# 2_RK3399_SDRAM.net
KiCad netlist of a schematic drawn in Altium Designer
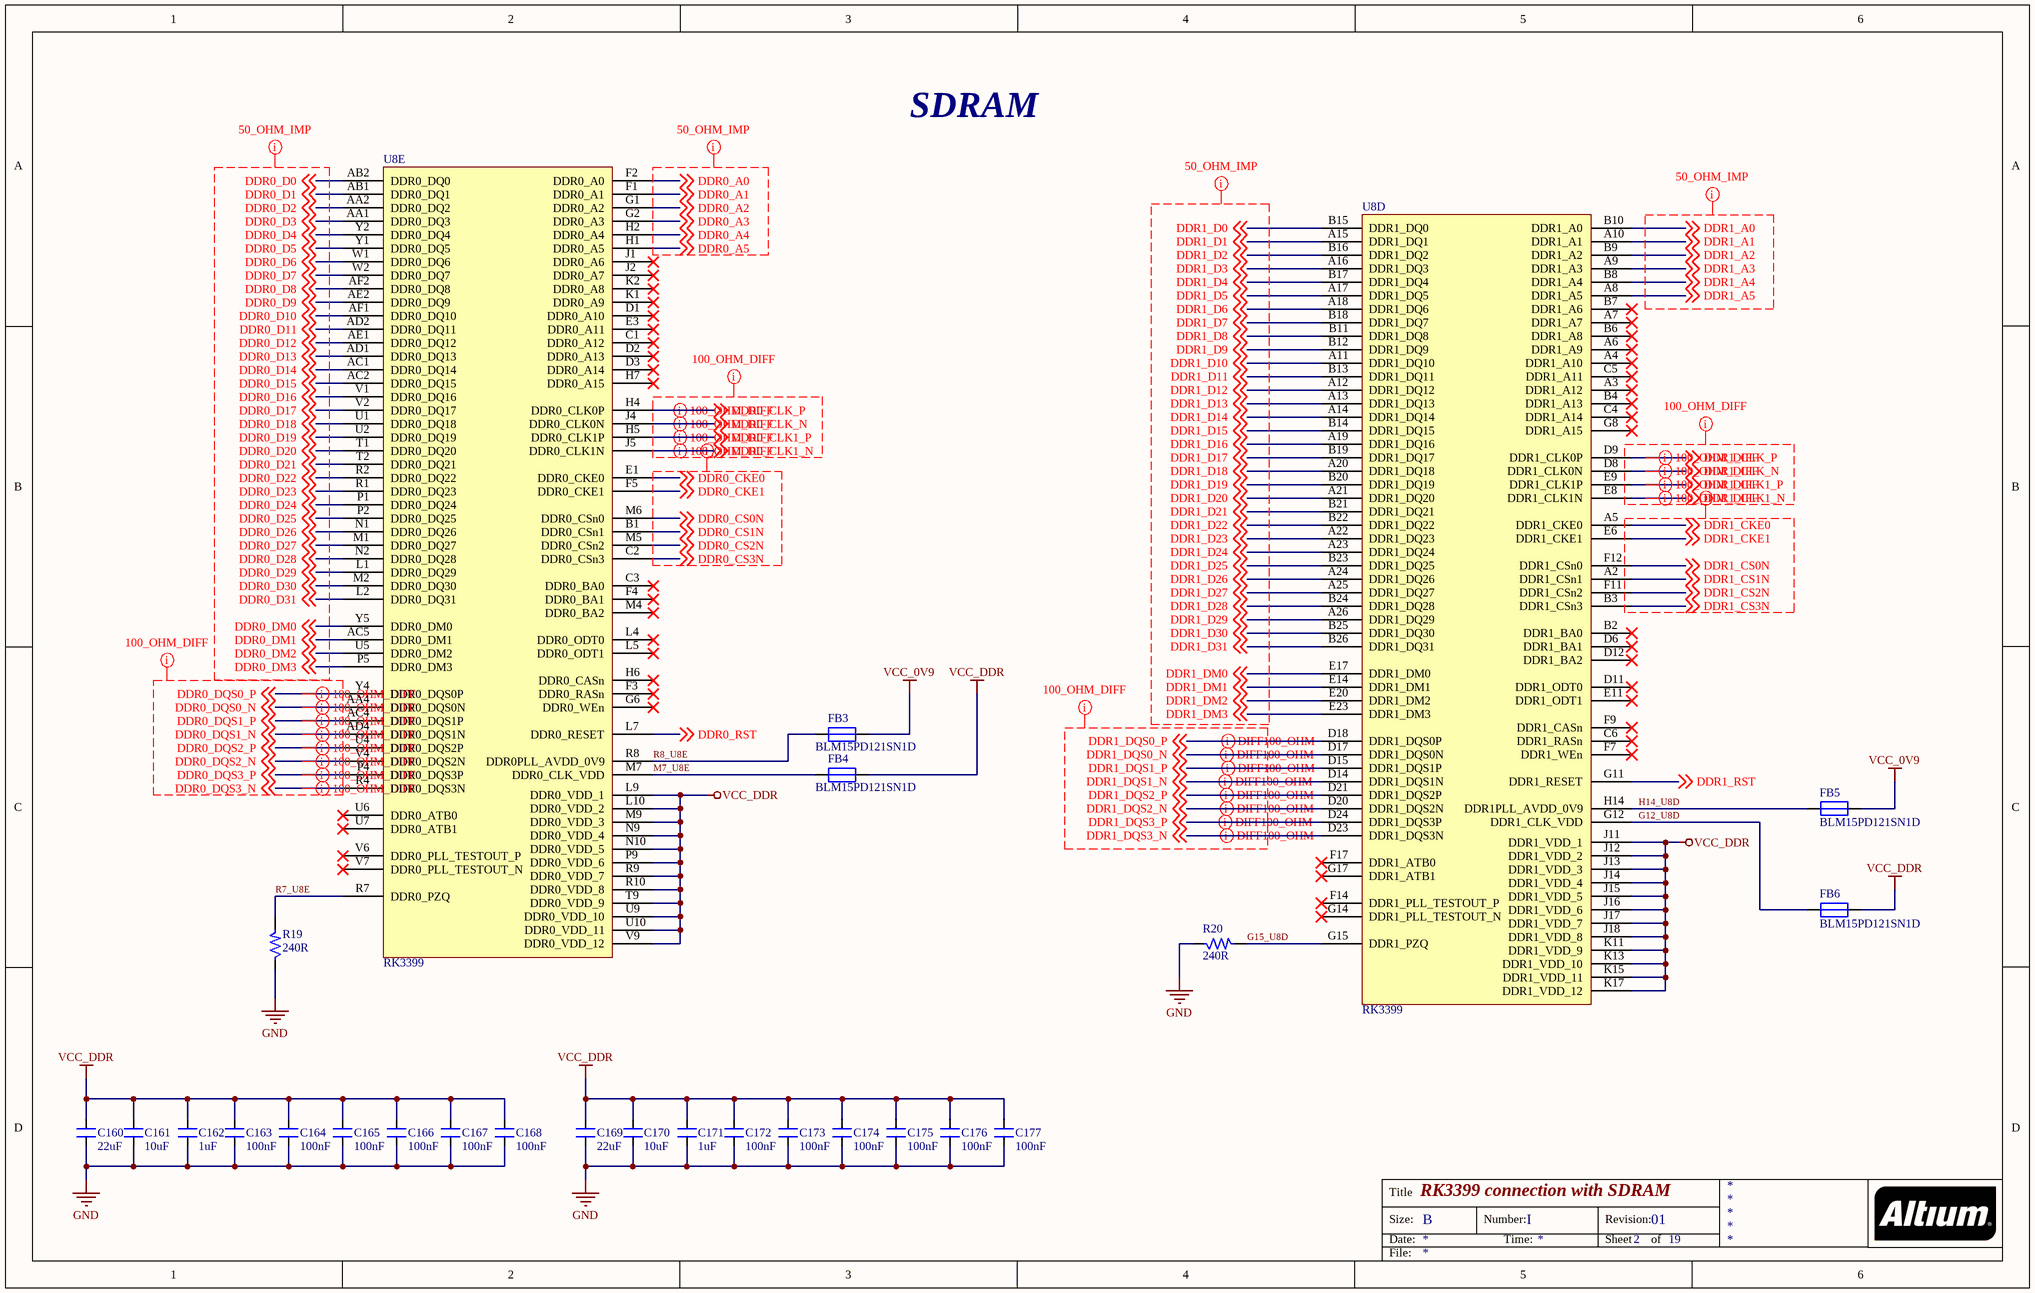
[diagram p0: [2] RK3399_SDRAM.SchDoc]

(export (version "E")
  (design (tool "Eeschema 10.0.6"))
  (components
    (comp (ref "C160")
      (value "22uF")
      (footprint "CAP_0402")
      (description "22µF ±20% 6.3V Ceramic Capacitor X5R 0402 (1005 Metric)")
      (fields
        (field (name "MANUFACTURER") "Murata Electronics")
        (field (name "MANUFACTURER PART NUMBER") "CL05A226MQ5N6J8")
      )
      (libsource (lib "EsteemPCB_SOM_Course_intlib") (part "CAP_22uF-6.3V-20%-0402"))
    )
    (comp (ref "C161")
      (value "10uF")
      (footprint "CAP_0402")
      (description "10µF ±20% 10V Ceramic Capacitor X5R 0402 (1005 Metric)")
      (fields
        (field (name "MANUFACTURER PART NUMBER") "CL05A106MP5NUNC")
        (field (name "MANUFACTURER") "Samsung Electro-Mechanics")
      )
      (libsource (lib "EsteemPCB_SOM_Course_intlib") (part "CAP_10uF-10V-20%-0402"))
    )
    (comp (ref "C162")
      (value "1uF")
      (footprint "CAP_0402")
      (description "1µF ±10% 10V Ceramic Capacitor X6S 0402 (1005 Metric)")
      (fields
        (field (name "MANUFACTURER") "Murata Electronics")
        (field (name "MANUFACTURER PART NUMBER") "GRT155C81A105KE01D")
      )
      (libsource (lib "EsteemPCB_SOM_Course_intlib") (part "CAP_1uF-10V-10%-0402"))
    )
    (comp (ref "C163")
      (value "100nF")
      (footprint "CAP_0402")
      (description "0.1µF ±10% 10V Ceramic Capacitor X7R 0402 (1005 Metric)")
      (fields
        (field (name "MANUFACTURER") "Yageo")
        (field (name "MANUFACTURER PART NUMBER") "CC0402KRX7R6BB104")
      )
      (libsource (lib "EsteemPCB_SOM_Course_intlib") (part "CAP_100nF-10V-10%-0402"))
    )
    (comp (ref "C164")
      (value "100nF")
      (footprint "CAP_0402")
      (description "0.1µF ±10% 10V Ceramic Capacitor X7R 0402 (1005 Metric)")
      (fields
        (field (name "MANUFACTURER") "Yageo")
        (field (name "MANUFACTURER PART NUMBER") "CC0402KRX7R6BB104")
      )
      (libsource (lib "EsteemPCB_SOM_Course_intlib") (part "CAP_100nF-10V-10%-0402"))
    )
    (comp (ref "C165")
      (value "100nF")
      (footprint "CAP_0402")
      (description "0.1µF ±10% 10V Ceramic Capacitor X7R 0402 (1005 Metric)")
      (fields
        (field (name "MANUFACTURER") "Yageo")
        (field (name "MANUFACTURER PART NUMBER") "CC0402KRX7R6BB104")
      )
      (libsource (lib "EsteemPCB_SOM_Course_intlib") (part "CAP_100nF-10V-10%-0402"))
    )
    (comp (ref "C166")
      (value "100nF")
      (footprint "CAP_0402")
      (description "0.1µF ±10% 10V Ceramic Capacitor X7R 0402 (1005 Metric)")
      (fields
        (field (name "MANUFACTURER") "Yageo")
        (field (name "MANUFACTURER PART NUMBER") "CC0402KRX7R6BB104")
      )
      (libsource (lib "EsteemPCB_SOM_Course_intlib") (part "CAP_100nF-10V-10%-0402"))
    )
    (comp (ref "C167")
      (value "100nF")
      (footprint "CAP_0402")
      (description "0.1µF ±10% 10V Ceramic Capacitor X7R 0402 (1005 Metric)")
      (fields
        (field (name "MANUFACTURER") "Yageo")
        (field (name "MANUFACTURER PART NUMBER") "CC0402KRX7R6BB104")
      )
      (libsource (lib "EsteemPCB_SOM_Course_intlib") (part "CAP_100nF-10V-10%-0402"))
    )
    (comp (ref "C168")
      (value "100nF")
      (footprint "CAP_0402")
      (description "0.1µF ±10% 10V Ceramic Capacitor X7R 0402 (1005 Metric)")
      (fields
        (field (name "MANUFACTURER") "Yageo")
        (field (name "MANUFACTURER PART NUMBER") "CC0402KRX7R6BB104")
      )
      (libsource (lib "EsteemPCB_SOM_Course_intlib") (part "CAP_100nF-10V-10%-0402"))
    )
    (comp (ref "C169")
      (value "22uF")
      (footprint "CAP_0402")
      (description "22µF ±20% 6.3V Ceramic Capacitor X5R 0402 (1005 Metric)")
      (fields
        (field (name "MANUFACTURER") "Murata Electronics")
        (field (name "MANUFACTURER PART NUMBER") "CL05A226MQ5N6J8")
      )
      (libsource (lib "EsteemPCB_SOM_Course_intlib") (part "CAP_22uF-6.3V-20%-0402"))
    )
    (comp (ref "C170")
      (value "10uF")
      (footprint "CAP_0402")
      (description "10µF ±20% 10V Ceramic Capacitor X5R 0402 (1005 Metric)")
      (fields
        (field (name "MANUFACTURER PART NUMBER") "CL05A106MP5NUNC")
        (field (name "MANUFACTURER") "Samsung Electro-Mechanics")
      )
      (libsource (lib "EsteemPCB_SOM_Course_intlib") (part "CAP_10uF-10V-20%-0402"))
    )
    (comp (ref "C171")
      (value "1uF")
      (footprint "CAP_0402")
      (description "1µF ±10% 10V Ceramic Capacitor X6S 0402 (1005 Metric)")
      (fields
        (field (name "MANUFACTURER") "Murata Electronics")
        (field (name "MANUFACTURER PART NUMBER") "GRT155C81A105KE01D")
      )
      (libsource (lib "EsteemPCB_SOM_Course_intlib") (part "CAP_1uF-10V-10%-0402"))
    )
    (comp (ref "C172")
      (value "100nF")
      (footprint "CAP_0402")
      (description "0.1µF ±10% 10V Ceramic Capacitor X7R 0402 (1005 Metric)")
      (fields
        (field (name "MANUFACTURER") "Yageo")
        (field (name "MANUFACTURER PART NUMBER") "CC0402KRX7R6BB104")
      )
      (libsource (lib "EsteemPCB_SOM_Course_intlib") (part "CAP_100nF-10V-10%-0402"))
    )
    (comp (ref "C173")
      (value "100nF")
      (footprint "CAP_0402")
      (description "0.1µF ±10% 10V Ceramic Capacitor X7R 0402 (1005 Metric)")
      (fields
        (field (name "MANUFACTURER") "Yageo")
        (field (name "MANUFACTURER PART NUMBER") "CC0402KRX7R6BB104")
      )
      (libsource (lib "EsteemPCB_SOM_Course_intlib") (part "CAP_100nF-10V-10%-0402"))
    )
    (comp (ref "C174")
      (value "100nF")
      (footprint "CAP_0402")
      (description "0.1µF ±10% 10V Ceramic Capacitor X7R 0402 (1005 Metric)")
      (fields
        (field (name "MANUFACTURER") "Yageo")
        (field (name "MANUFACTURER PART NUMBER") "CC0402KRX7R6BB104")
      )
      (libsource (lib "EsteemPCB_SOM_Course_intlib") (part "CAP_100nF-10V-10%-0402"))
    )
    (comp (ref "C175")
      (value "100nF")
      (footprint "CAP_0402")
      (description "0.1µF ±10% 10V Ceramic Capacitor X7R 0402 (1005 Metric)")
      (fields
        (field (name "MANUFACTURER") "Yageo")
        (field (name "MANUFACTURER PART NUMBER") "CC0402KRX7R6BB104")
      )
      (libsource (lib "EsteemPCB_SOM_Course_intlib") (part "CAP_100nF-10V-10%-0402"))
    )
    (comp (ref "C176")
      (value "100nF")
      (footprint "CAP_0402")
      (description "0.1µF ±10% 10V Ceramic Capacitor X7R 0402 (1005 Metric)")
      (fields
        (field (name "MANUFACTURER") "Yageo")
        (field (name "MANUFACTURER PART NUMBER") "CC0402KRX7R6BB104")
      )
      (libsource (lib "EsteemPCB_SOM_Course_intlib") (part "CAP_100nF-10V-10%-0402"))
    )
    (comp (ref "C177")
      (value "100nF")
      (footprint "CAP_0402")
      (description "0.1µF ±10% 10V Ceramic Capacitor X7R 0402 (1005 Metric)")
      (fields
        (field (name "MANUFACTURER") "Yageo")
        (field (name "MANUFACTURER PART NUMBER") "CC0402KRX7R6BB104")
      )
      (libsource (lib "EsteemPCB_SOM_Course_intlib") (part "CAP_100nF-10V-10%-0402"))
    )
    (comp (ref "FB3")
      (value "BLM15PD121SN1D")
      (footprint "RES_0402")
      (description "120 Ohms @ 100MHz 1 Power Line Ferrite Bead 0402 (1005 Metric) 1.3A 90mOhm")
      (fields (field (name "MANUFACTURER") "Murata Electronics"))
      (libsource (lib "EsteemPCB_SOM_Course_intlib") (part "FB_120R-1.3A-100Mhz-0402"))
    )
    (comp (ref "FB4")
      (value "BLM15PD121SN1D")
      (footprint "RES_0402")
      (description "120 Ohms @ 100MHz 1 Power Line Ferrite Bead 0402 (1005 Metric) 1.3A 90mOhm")
      (fields (field (name "MANUFACTURER") "Murata Electronics"))
      (libsource (lib "EsteemPCB_SOM_Course_intlib") (part "FB_120R-1.3A-100Mhz-0402"))
    )
    (comp (ref "FB5")
      (value "BLM15PD121SN1D")
      (footprint "RES_0402")
      (description "120 Ohms @ 100MHz 1 Power Line Ferrite Bead 0402 (1005 Metric) 1.3A 90mOhm")
      (fields (field (name "MANUFACTURER") "Murata Electronics"))
      (libsource (lib "EsteemPCB_SOM_Course_intlib") (part "FB_120R-1.3A-100Mhz-0402"))
    )
    (comp (ref "FB6")
      (value "BLM15PD121SN1D")
      (footprint "RES_0402")
      (description "120 Ohms @ 100MHz 1 Power Line Ferrite Bead 0402 (1005 Metric) 1.3A 90mOhm")
      (fields (field (name "MANUFACTURER") "Murata Electronics"))
      (libsource (lib "EsteemPCB_SOM_Course_intlib") (part "FB_120R-1.3A-100Mhz-0402"))
    )
    (comp (ref "R19")
      (value "240R")
      (footprint "RES_0201")
      (description "240 Ohms ±1% 0.05W, 1/20W Chip Resistor 0201 (0603 Metric) Thick Film")
      (fields
        (field (name "MANUFACTURER") "Yageo")
        (field (name "MANUFACTURER PART NUMBER") "RC0201FR-07240RL")
      )
      (libsource (lib "EsteemPCB_SOM_Course_intlib") (part "RES_240R-0.05W-1%-0201"))
    )
    (comp (ref "R20")
      (value "240R")
      (footprint "RES_0201")
      (description "240 Ohms ±1% 0.05W, 1/20W Chip Resistor 0201 (0603 Metric) Thick Film")
      (fields
        (field (name "MANUFACTURER") "Yageo")
        (field (name "MANUFACTURER PART NUMBER") "RC0201FR-07240RL")
      )
      (libsource (lib "EsteemPCB_SOM_Course_intlib") (part "RES_240R-0.05W-1%-0201"))
    )
    (comp (ref "U8")
      (value "RK3399")
      (footprint "FBGA828_23_826X826")
      (description "RK3399 is a low power, high performance processor for computing, personal mobile.")
      (fields (field (name "MANUFACTURER") "Rockchip"))
      (libsource (lib "EsteemPCB_SOM_Course_intlib") (part "IC_RK3399-FCBGA828"))
    )
  )
  (nets
    (net (code "1") (name "/G12_U8D") (class "Default")
      (node (ref "FB6") (pin "1") (pinfunction "1_1") (pintype "passive"))
      (node (ref "U8") (pin "G12") (pinfunction "DDR1_CLK_VDD_G12") (pintype "passive"))
    )
    (net (code "2") (name "/G15_U8D") (class "Default")
      (node (ref "R20") (pin "2") (pinfunction "2_2") (pintype "passive"))
      (node (ref "U8") (pin "G15") (pinfunction "DDR1_PZQ_G15") (pintype "passive"))
    )
    (net (code "3") (name "/H14_U8D") (class "Default")
      (node (ref "FB5") (pin "1") (pinfunction "1_1") (pintype "passive"))
      (node (ref "U8") (pin "H14") (pinfunction "DDR1PLL_AVDD_0V9_H14") (pintype "passive"))
    )
    (net (code "4") (name "/M7_U8E") (class "Default")
      (node (ref "FB4") (pin "1") (pinfunction "1_1") (pintype "passive"))
      (node (ref "U8") (pin "M7") (pinfunction "DDR0_CLK_VDD_M7") (pintype "passive"))
    )
    (net (code "5") (name "/R7_U8E") (class "Default")
      (node (ref "R19") (pin "2") (pinfunction "2_2") (pintype "passive"))
      (node (ref "U8") (pin "R7") (pinfunction "DDR0_PZQ_R7") (pintype "passive"))
    )
    (net (code "6") (name "/R8_U8E") (class "Default")
      (node (ref "FB3") (pin "1") (pinfunction "1_1") (pintype "passive"))
      (node (ref "U8") (pin "R8") (pinfunction "DDR0PLL_AVDD_0V9_R8") (pintype "passive"))
    )
    (net (code "7") (name "DDR0_A0") (class "Default")
      (node (ref "U8") (pin "F2") (pinfunction "DDR0_A0_F2") (pintype "passive"))
    )
    (net (code "8") (name "DDR0_A1") (class "Default")
      (node (ref "U8") (pin "F1") (pinfunction "DDR0_A1_F1") (pintype "passive"))
    )
    (net (code "9") (name "DDR0_A2") (class "Default")
      (node (ref "U8") (pin "G1") (pinfunction "DDR0_A2_G1") (pintype "passive"))
    )
    (net (code "10") (name "DDR0_A3") (class "Default")
      (node (ref "U8") (pin "G2") (pinfunction "DDR0_A3_G2") (pintype "passive"))
    )
    (net (code "11") (name "DDR0_A4") (class "Default")
      (node (ref "U8") (pin "H2") (pinfunction "DDR0_A4_H2") (pintype "passive"))
    )
    (net (code "12") (name "DDR0_A5") (class "Default")
      (node (ref "U8") (pin "H1") (pinfunction "DDR0_A5_H1") (pintype "passive"))
    )
    (net (code "13") (name "DDR0_CKE0") (class "Default")
      (node (ref "U8") (pin "E1") (pinfunction "DDR0_CKE0_E1") (pintype "passive"))
    )
    (net (code "14") (name "DDR0_CKE1") (class "Default")
      (node (ref "U8") (pin "F5") (pinfunction "DDR0_CKE1_F5") (pintype "passive"))
    )
    (net (code "15") (name "DDR0_CLK1_N") (class "Default")
      (node (ref "U8") (pin "J5") (pinfunction "DDR0_CLK1N_J5") (pintype "passive"))
    )
    (net (code "16") (name "DDR0_CLK1_P") (class "Default")
      (node (ref "U8") (pin "H5") (pinfunction "DDR0_CLK1P_H5") (pintype "passive"))
    )
    (net (code "17") (name "DDR0_CLK_N") (class "Default")
      (node (ref "U8") (pin "J4") (pinfunction "DDR0_CLK0N_J4") (pintype "passive"))
    )
    (net (code "18") (name "DDR0_CLK_P") (class "Default")
      (node (ref "U8") (pin "H4") (pinfunction "DDR0_CLK0P_H4") (pintype "passive"))
    )
    (net (code "19") (name "DDR0_CS0N") (class "Default")
      (node (ref "U8") (pin "M6") (pinfunction "DDR0_CSn0_M6") (pintype "passive"))
    )
    (net (code "20") (name "DDR0_CS1N") (class "Default")
      (node (ref "U8") (pin "B1") (pinfunction "DDR0_CSn1_B1") (pintype "passive"))
    )
    (net (code "21") (name "DDR0_CS2N") (class "Default")
      (node (ref "U8") (pin "M5") (pinfunction "DDR0_CSn2_M5") (pintype "passive"))
    )
    (net (code "22") (name "DDR0_CS3N") (class "Default")
      (node (ref "U8") (pin "C2") (pinfunction "DDR0_CSn3_C2") (pintype "passive"))
    )
    (net (code "23") (name "DDR0_D0") (class "Default")
      (node (ref "U8") (pin "AB2") (pinfunction "DDR0_DQ0_AB2") (pintype "passive"))
    )
    (net (code "24") (name "DDR0_D1") (class "Default")
      (node (ref "U8") (pin "AB1") (pinfunction "DDR0_DQ1_AB1") (pintype "passive"))
    )
    (net (code "25") (name "DDR0_D2") (class "Default")
      (node (ref "U8") (pin "AA2") (pinfunction "DDR0_DQ2_AA2") (pintype "passive"))
    )
    (net (code "26") (name "DDR0_D3") (class "Default")
      (node (ref "U8") (pin "AA1") (pinfunction "DDR0_DQ3_AA1") (pintype "passive"))
    )
    (net (code "27") (name "DDR0_D4") (class "Default")
      (node (ref "U8") (pin "Y2") (pinfunction "DDR0_DQ4_Y2") (pintype "passive"))
    )
    (net (code "28") (name "DDR0_D5") (class "Default")
      (node (ref "U8") (pin "Y1") (pinfunction "DDR0_DQ5_Y1") (pintype "passive"))
    )
    (net (code "29") (name "DDR0_D6") (class "Default")
      (node (ref "U8") (pin "W1") (pinfunction "DDR0_DQ6_W1") (pintype "passive"))
    )
    (net (code "30") (name "DDR0_D7") (class "Default")
      (node (ref "U8") (pin "W2") (pinfunction "DDR0_DQ7_W2") (pintype "passive"))
    )
    (net (code "31") (name "DDR0_D8") (class "Default")
      (node (ref "U8") (pin "AF2") (pinfunction "DDR0_DQ8_AF2") (pintype "passive"))
    )
    (net (code "32") (name "DDR0_D9") (class "Default")
      (node (ref "U8") (pin "AE2") (pinfunction "DDR0_DQ9_AE2") (pintype "passive"))
    )
    (net (code "33") (name "DDR0_D10") (class "Default")
      (node (ref "U8") (pin "AF1") (pinfunction "DDR0_DQ10_AF1") (pintype "passive"))
    )
    (net (code "34") (name "DDR0_D11") (class "Default")
      (node (ref "U8") (pin "AD2") (pinfunction "DDR0_DQ11_AD2") (pintype "passive"))
    )
    (net (code "35") (name "DDR0_D12") (class "Default")
      (node (ref "U8") (pin "AE1") (pinfunction "DDR0_DQ12_AE1") (pintype "passive"))
    )
    (net (code "36") (name "DDR0_D13") (class "Default")
      (node (ref "U8") (pin "AD1") (pinfunction "DDR0_DQ13_AD1") (pintype "passive"))
    )
    (net (code "37") (name "DDR0_D14") (class "Default")
      (node (ref "U8") (pin "AC1") (pinfunction "DDR0_DQ14_AC1") (pintype "passive"))
    )
    (net (code "38") (name "DDR0_D15") (class "Default")
      (node (ref "U8") (pin "AC2") (pinfunction "DDR0_DQ15_AC2") (pintype "passive"))
    )
    (net (code "39") (name "DDR0_D16") (class "Default")
      (node (ref "U8") (pin "V1") (pinfunction "DDR0_DQ16_V1") (pintype "passive"))
    )
    (net (code "40") (name "DDR0_D17") (class "Default")
      (node (ref "U8") (pin "V2") (pinfunction "DDR0_DQ17_V2") (pintype "passive"))
    )
    (net (code "41") (name "DDR0_D18") (class "Default")
      (node (ref "U8") (pin "U1") (pinfunction "DDR0_DQ18_U1") (pintype "passive"))
    )
    (net (code "42") (name "DDR0_D19") (class "Default")
      (node (ref "U8") (pin "U2") (pinfunction "DDR0_DQ19_U2") (pintype "passive"))
    )
    (net (code "43") (name "DDR0_D20") (class "Default")
      (node (ref "U8") (pin "T1") (pinfunction "DDR0_DQ20_T1") (pintype "passive"))
    )
    (net (code "44") (name "DDR0_D21") (class "Default")
      (node (ref "U8") (pin "T2") (pinfunction "DDR0_DQ21_T2") (pintype "passive"))
    )
    (net (code "45") (name "DDR0_D22") (class "Default")
      (node (ref "U8") (pin "R2") (pinfunction "DDR0_DQ22_R2") (pintype "passive"))
    )
    (net (code "46") (name "DDR0_D23") (class "Default")
      (node (ref "U8") (pin "R1") (pinfunction "DDR0_DQ23_R1") (pintype "passive"))
    )
    (net (code "47") (name "DDR0_D24") (class "Default")
      (node (ref "U8") (pin "P1") (pinfunction "DDR0_DQ24_P1") (pintype "passive"))
    )
    (net (code "48") (name "DDR0_D25") (class "Default")
      (node (ref "U8") (pin "P2") (pinfunction "DDR0_DQ25_P2") (pintype "passive"))
    )
    (net (code "49") (name "DDR0_D26") (class "Default")
      (node (ref "U8") (pin "N1") (pinfunction "DDR0_DQ26_N1") (pintype "passive"))
    )
    (net (code "50") (name "DDR0_D27") (class "Default")
      (node (ref "U8") (pin "M1") (pinfunction "DDR0_DQ27_M1") (pintype "passive"))
    )
    (net (code "51") (name "DDR0_D28") (class "Default")
      (node (ref "U8") (pin "N2") (pinfunction "DDR0_DQ28_N2") (pintype "passive"))
    )
    (net (code "52") (name "DDR0_D29") (class "Default")
      (node (ref "U8") (pin "L1") (pinfunction "DDR0_DQ29_L1") (pintype "passive"))
    )
    (net (code "53") (name "DDR0_D30") (class "Default")
      (node (ref "U8") (pin "M2") (pinfunction "DDR0_DQ30_M2") (pintype "passive"))
    )
    (net (code "54") (name "DDR0_D31") (class "Default")
      (node (ref "U8") (pin "L2") (pinfunction "DDR0_DQ31_L2") (pintype "passive"))
    )
    (net (code "55") (name "DDR0_DM0") (class "Default")
      (node (ref "U8") (pin "Y5") (pinfunction "DDR0_DM0_Y5") (pintype "passive"))
    )
    (net (code "56") (name "DDR0_DM1") (class "Default")
      (node (ref "U8") (pin "AC5") (pinfunction "DDR0_DM1_AC5") (pintype "passive"))
    )
    (net (code "57") (name "DDR0_DM2") (class "Default")
      (node (ref "U8") (pin "U5") (pinfunction "DDR0_DM2_U5") (pintype "passive"))
    )
    (net (code "58") (name "DDR0_DM3") (class "Default")
      (node (ref "U8") (pin "P5") (pinfunction "DDR0_DM3_P5") (pintype "passive"))
    )
    (net (code "59") (name "DDR0_DQS0_N") (class "Default")
      (node (ref "U8") (pin "AA4") (pinfunction "DDR0_DQS0N_AA4") (pintype "passive"))
    )
    (net (code "60") (name "DDR0_DQS0_P") (class "Default")
      (node (ref "U8") (pin "Y4") (pinfunction "DDR0_DQS0P_Y4") (pintype "passive"))
    )
    (net (code "61") (name "DDR0_DQS1_N") (class "Default")
      (node (ref "U8") (pin "AD4") (pinfunction "DDR0_DQS1N_AD4") (pintype "passive"))
    )
    (net (code "62") (name "DDR0_DQS1_P") (class "Default")
      (node (ref "U8") (pin "AC4") (pinfunction "DDR0_DQS1P_AC4") (pintype "passive"))
    )
    (net (code "63") (name "DDR0_DQS2_N") (class "Default")
      (node (ref "U8") (pin "V4") (pinfunction "DDR0_DQS2N_V4") (pintype "passive"))
    )
    (net (code "64") (name "DDR0_DQS2_P") (class "Default")
      (node (ref "U8") (pin "U4") (pinfunction "DDR0_DQS2P_U4") (pintype "passive"))
    )
    (net (code "65") (name "DDR0_DQS3_N") (class "Default")
      (node (ref "U8") (pin "R4") (pinfunction "DDR0_DQS3N_R4") (pintype "passive"))
    )
    (net (code "66") (name "DDR0_DQS3_P") (class "Default")
      (node (ref "U8") (pin "P4") (pinfunction "DDR0_DQS3P_P4") (pintype "passive"))
    )
    (net (code "67") (name "DDR0_RST") (class "Default")
      (node (ref "U8") (pin "L7") (pinfunction "DDR0_RESET_L7") (pintype "passive"))
    )
    (net (code "68") (name "DDR1_A0") (class "Default")
      (node (ref "U8") (pin "B10") (pinfunction "DDR1_A0_B10") (pintype "passive"))
    )
    (net (code "69") (name "DDR1_A1") (class "Default")
      (node (ref "U8") (pin "A10") (pinfunction "DDR1_A1_A10") (pintype "passive"))
    )
    (net (code "70") (name "DDR1_A2") (class "Default")
      (node (ref "U8") (pin "B9") (pinfunction "DDR1_A2_B9") (pintype "passive"))
    )
    (net (code "71") (name "DDR1_A3") (class "Default")
      (node (ref "U8") (pin "A9") (pinfunction "DDR1_A3_A9") (pintype "passive"))
    )
    (net (code "72") (name "DDR1_A4") (class "Default")
      (node (ref "U8") (pin "B8") (pinfunction "DDR1_A4_B8") (pintype "passive"))
    )
    (net (code "73") (name "DDR1_A5") (class "Default")
      (node (ref "U8") (pin "A8") (pinfunction "DDR1_A5_A8") (pintype "passive"))
    )
    (net (code "74") (name "DDR1_CKE0") (class "Default")
      (node (ref "U8") (pin "A5") (pinfunction "DDR1_CKE0_A5") (pintype "passive"))
    )
    (net (code "75") (name "DDR1_CKE1") (class "Default")
      (node (ref "U8") (pin "E6") (pinfunction "DDR1_CKE1_E6") (pintype "passive"))
    )
    (net (code "76") (name "DDR1_CLK1_N") (class "Default")
      (node (ref "U8") (pin "E8") (pinfunction "DDR1_CLK1N_E8") (pintype "passive"))
    )
    (net (code "77") (name "DDR1_CLK1_P") (class "Default")
      (node (ref "U8") (pin "E9") (pinfunction "DDR1_CLK1P_E9") (pintype "passive"))
    )
    (net (code "78") (name "DDR1_CLK_N") (class "Default")
      (node (ref "U8") (pin "D8") (pinfunction "DDR1_CLK0N_D8") (pintype "passive"))
    )
    (net (code "79") (name "DDR1_CLK_P") (class "Default")
      (node (ref "U8") (pin "D9") (pinfunction "DDR1_CLK0P_D9") (pintype "passive"))
    )
    (net (code "80") (name "DDR1_CS0N") (class "Default")
      (node (ref "U8") (pin "F12") (pinfunction "DDR1_CSn0_F12") (pintype "passive"))
    )
    (net (code "81") (name "DDR1_CS1N") (class "Default")
      (node (ref "U8") (pin "A2") (pinfunction "DDR1_CSn1_A2") (pintype "passive"))
    )
    (net (code "82") (name "DDR1_CS2N") (class "Default")
      (node (ref "U8") (pin "F11") (pinfunction "DDR1_CSn2_F11") (pintype "passive"))
    )
    (net (code "83") (name "DDR1_CS3N") (class "Default")
      (node (ref "U8") (pin "B3") (pinfunction "DDR1_CSn3_B3") (pintype "passive"))
    )
    (net (code "84") (name "DDR1_D0") (class "Default")
      (node (ref "U8") (pin "B15") (pinfunction "DDR1_DQ0_B15") (pintype "passive"))
    )
    (net (code "85") (name "DDR1_D1") (class "Default")
      (node (ref "U8") (pin "A15") (pinfunction "DDR1_DQ1_A15") (pintype "passive"))
    )
    (net (code "86") (name "DDR1_D2") (class "Default")
      (node (ref "U8") (pin "B16") (pinfunction "DDR1_DQ2_B16") (pintype "passive"))
    )
    (net (code "87") (name "DDR1_D3") (class "Default")
      (node (ref "U8") (pin "A16") (pinfunction "DDR1_DQ3_A16") (pintype "passive"))
    )
    (net (code "88") (name "DDR1_D4") (class "Default")
      (node (ref "U8") (pin "B17") (pinfunction "DDR1_DQ4_B17") (pintype "passive"))
    )
    (net (code "89") (name "DDR1_D5") (class "Default")
      (node (ref "U8") (pin "A17") (pinfunction "DDR1_DQ5_A17") (pintype "passive"))
    )
    (net (code "90") (name "DDR1_D6") (class "Default")
      (node (ref "U8") (pin "A18") (pinfunction "DDR1_DQ6_A18") (pintype "passive"))
    )
    (net (code "91") (name "DDR1_D7") (class "Default")
      (node (ref "U8") (pin "B18") (pinfunction "DDR1_DQ7_B18") (pintype "passive"))
    )
    (net (code "92") (name "DDR1_D8") (class "Default")
      (node (ref "U8") (pin "B11") (pinfunction "DDR1_DQ8_B11") (pintype "passive"))
    )
    (net (code "93") (name "DDR1_D9") (class "Default")
      (node (ref "U8") (pin "B12") (pinfunction "DDR1_DQ9_B12") (pintype "passive"))
    )
    (net (code "94") (name "DDR1_D10") (class "Default")
      (node (ref "U8") (pin "A11") (pinfunction "DDR1_DQ10_A11") (pintype "passive"))
    )
    (net (code "95") (name "DDR1_D11") (class "Default")
      (node (ref "U8") (pin "B13") (pinfunction "DDR1_DQ11_B13") (pintype "passive"))
    )
    (net (code "96") (name "DDR1_D12") (class "Default")
      (node (ref "U8") (pin "A12") (pinfunction "DDR1_DQ12_A12") (pintype "passive"))
    )
    (net (code "97") (name "DDR1_D13") (class "Default")
      (node (ref "U8") (pin "A13") (pinfunction "DDR1_DQ13_A13") (pintype "passive"))
    )
    (net (code "98") (name "DDR1_D14") (class "Default")
      (node (ref "U8") (pin "A14") (pinfunction "DDR1_DQ14_A14") (pintype "passive"))
    )
    (net (code "99") (name "DDR1_D15") (class "Default")
      (node (ref "U8") (pin "B14") (pinfunction "DDR1_DQ15_B14") (pintype "passive"))
    )
    (net (code "100") (name "DDR1_D16") (class "Default")
      (node (ref "U8") (pin "A19") (pinfunction "DDR1_DQ16_A19") (pintype "passive"))
    )
    (net (code "101") (name "DDR1_D17") (class "Default")
      (node (ref "U8") (pin "B19") (pinfunction "DDR1_DQ17_B19") (pintype "passive"))
    )
    (net (code "102") (name "DDR1_D18") (class "Default")
      (node (ref "U8") (pin "A20") (pinfunction "DDR1_DQ18_A20") (pintype "passive"))
    )
    (net (code "103") (name "DDR1_D19") (class "Default")
      (node (ref "U8") (pin "B20") (pinfunction "DDR1_DQ19_B20") (pintype "passive"))
    )
    (net (code "104") (name "DDR1_D20") (class "Default")
      (node (ref "U8") (pin "A21") (pinfunction "DDR1_DQ20_A21") (pintype "passive"))
    )
    (net (code "105") (name "DDR1_D21") (class "Default")
      (node (ref "U8") (pin "B21") (pinfunction "DDR1_DQ21_B21") (pintype "passive"))
    )
    (net (code "106") (name "DDR1_D22") (class "Default")
      (node (ref "U8") (pin "B22") (pinfunction "DDR1_DQ22_B22") (pintype "passive"))
    )
    (net (code "107") (name "DDR1_D23") (class "Default")
      (node (ref "U8") (pin "A22") (pinfunction "DDR1_DQ23_A22") (pintype "passive"))
    )
    (net (code "108") (name "DDR1_D24") (class "Default")
      (node (ref "U8") (pin "A23") (pinfunction "DDR1_DQ24_A23") (pintype "passive"))
    )
    (net (code "109") (name "DDR1_D25") (class "Default")
      (node (ref "U8") (pin "B23") (pinfunction "DDR1_DQ25_B23") (pintype "passive"))
    )
    (net (code "110") (name "DDR1_D26") (class "Default")
      (node (ref "U8") (pin "A24") (pinfunction "DDR1_DQ26_A24") (pintype "passive"))
    )
    (net (code "111") (name "DDR1_D27") (class "Default")
      (node (ref "U8") (pin "A25") (pinfunction "DDR1_DQ27_A25") (pintype "passive"))
    )
    (net (code "112") (name "DDR1_D28") (class "Default")
      (node (ref "U8") (pin "B24") (pinfunction "DDR1_DQ28_B24") (pintype "passive"))
    )
    (net (code "113") (name "DDR1_D29") (class "Default")
      (node (ref "U8") (pin "A26") (pinfunction "DDR1_DQ29_A26") (pintype "passive"))
    )
    (net (code "114") (name "DDR1_D30") (class "Default")
      (node (ref "U8") (pin "B25") (pinfunction "DDR1_DQ30_B25") (pintype "passive"))
    )
    (net (code "115") (name "DDR1_D31") (class "Default")
      (node (ref "U8") (pin "B26") (pinfunction "DDR1_DQ31_B26") (pintype "passive"))
    )
    (net (code "116") (name "DDR1_DM0") (class "Default")
      (node (ref "U8") (pin "E17") (pinfunction "DDR1_DM0_E17") (pintype "passive"))
    )
    (net (code "117") (name "DDR1_DM1") (class "Default")
      (node (ref "U8") (pin "E14") (pinfunction "DDR1_DM1_E14") (pintype "passive"))
    )
    (net (code "118") (name "DDR1_DM2") (class "Default")
      (node (ref "U8") (pin "E20") (pinfunction "DDR1_DM2_E20") (pintype "passive"))
    )
    (net (code "119") (name "DDR1_DM3") (class "Default")
      (node (ref "U8") (pin "E23") (pinfunction "DDR1_DM3_E23") (pintype "passive"))
    )
    (net (code "120") (name "DDR1_DQS0_N") (class "Default")
      (node (ref "U8") (pin "D17") (pinfunction "DDR1_DQS0N_D17") (pintype "passive"))
    )
    (net (code "121") (name "DDR1_DQS0_P") (class "Default")
      (node (ref "U8") (pin "D18") (pinfunction "DDR1_DQS0P_D18") (pintype "passive"))
    )
    (net (code "122") (name "DDR1_DQS1_N") (class "Default")
      (node (ref "U8") (pin "D14") (pinfunction "DDR1_DQS1N_D14") (pintype "passive"))
    )
    (net (code "123") (name "DDR1_DQS1_P") (class "Default")
      (node (ref "U8") (pin "D15") (pinfunction "DDR1_DQS1P_D15") (pintype "passive"))
    )
    (net (code "124") (name "DDR1_DQS2_N") (class "Default")
      (node (ref "U8") (pin "D20") (pinfunction "DDR1_DQS2N_D20") (pintype "passive"))
    )
    (net (code "125") (name "DDR1_DQS2_P") (class "Default")
      (node (ref "U8") (pin "D21") (pinfunction "DDR1_DQS2P_D21") (pintype "passive"))
    )
    (net (code "126") (name "DDR1_DQS3_N") (class "Default")
      (node (ref "U8") (pin "D23") (pinfunction "DDR1_DQS3N_D23") (pintype "passive"))
    )
    (net (code "127") (name "DDR1_DQS3_P") (class "Default")
      (node (ref "U8") (pin "D24") (pinfunction "DDR1_DQS3P_D24") (pintype "passive"))
    )
    (net (code "128") (name "DDR1_RST") (class "Default")
      (node (ref "U8") (pin "G11") (pinfunction "DDR1_RESET_G11") (pintype "passive"))
    )
    (net (code "129") (name "GND") (class "Default")
      (node (ref "C160") (pin "1") (pinfunction "1_1") (pintype "passive"))
      (node (ref "C161") (pin "1") (pinfunction "1_1") (pintype "passive"))
      (node (ref "C162") (pin "1") (pinfunction "1_1") (pintype "passive"))
      (node (ref "C163") (pin "1") (pinfunction "1_1") (pintype "passive"))
      (node (ref "C164") (pin "1") (pinfunction "1_1") (pintype "passive"))
      (node (ref "C165") (pin "1") (pinfunction "1_1") (pintype "passive"))
      (node (ref "C166") (pin "1") (pinfunction "1_1") (pintype "passive"))
      (node (ref "C167") (pin "1") (pinfunction "1_1") (pintype "passive"))
      (node (ref "C168") (pin "1") (pinfunction "1_1") (pintype "passive"))
      (node (ref "C169") (pin "1") (pinfunction "1_1") (pintype "passive"))
      (node (ref "C170") (pin "1") (pinfunction "1_1") (pintype "passive"))
      (node (ref "C171") (pin "1") (pinfunction "1_1") (pintype "passive"))
      (node (ref "C172") (pin "1") (pinfunction "1_1") (pintype "passive"))
      (node (ref "C173") (pin "1") (pinfunction "1_1") (pintype "passive"))
      (node (ref "C174") (pin "1") (pinfunction "1_1") (pintype "passive"))
      (node (ref "C175") (pin "1") (pinfunction "1_1") (pintype "passive"))
      (node (ref "C176") (pin "1") (pinfunction "1_1") (pintype "passive"))
      (node (ref "C177") (pin "1") (pinfunction "1_1") (pintype "passive"))
      (node (ref "R19") (pin "1") (pinfunction "1_1") (pintype "passive"))
      (node (ref "R20") (pin "1") (pinfunction "1_1") (pintype "passive"))
    )
    (net (code "130") (name "VCC_0V9") (class "Default")
      (node (ref "FB3") (pin "2") (pinfunction "2_2") (pintype "passive"))
      (node (ref "FB5") (pin "2") (pinfunction "2_2") (pintype "passive"))
    )
    (net (code "131") (name "VCC_DDR") (class "Default")
      (node (ref "C160") (pin "2") (pinfunction "2_2") (pintype "passive"))
      (node (ref "C161") (pin "2") (pinfunction "2_2") (pintype "passive"))
      (node (ref "C162") (pin "2") (pinfunction "2_2") (pintype "passive"))
      (node (ref "C163") (pin "2") (pinfunction "2_2") (pintype "passive"))
      (node (ref "C164") (pin "2") (pinfunction "2_2") (pintype "passive"))
      (node (ref "C165") (pin "2") (pinfunction "2_2") (pintype "passive"))
      (node (ref "C166") (pin "2") (pinfunction "2_2") (pintype "passive"))
      (node (ref "C167") (pin "2") (pinfunction "2_2") (pintype "passive"))
      (node (ref "C168") (pin "2") (pinfunction "2_2") (pintype "passive"))
      (node (ref "C169") (pin "2") (pinfunction "2_2") (pintype "passive"))
      (node (ref "C170") (pin "2") (pinfunction "2_2") (pintype "passive"))
      (node (ref "C171") (pin "2") (pinfunction "2_2") (pintype "passive"))
      (node (ref "C172") (pin "2") (pinfunction "2_2") (pintype "passive"))
      (node (ref "C173") (pin "2") (pinfunction "2_2") (pintype "passive"))
      (node (ref "C174") (pin "2") (pinfunction "2_2") (pintype "passive"))
      (node (ref "C175") (pin "2") (pinfunction "2_2") (pintype "passive"))
      (node (ref "C176") (pin "2") (pinfunction "2_2") (pintype "passive"))
      (node (ref "C177") (pin "2") (pinfunction "2_2") (pintype "passive"))
      (node (ref "FB4") (pin "2") (pinfunction "2_2") (pintype "passive"))
      (node (ref "FB6") (pin "2") (pinfunction "2_2") (pintype "passive"))
      (node (ref "U8") (pin "J11") (pinfunction "DDR1_VDD_1_J11") (pintype "passive"))
      (node (ref "U8") (pin "J12") (pinfunction "DDR1_VDD_2_J12") (pintype "passive"))
      (node (ref "U8") (pin "J13") (pinfunction "DDR1_VDD_3_J13") (pintype "passive"))
      (node (ref "U8") (pin "J14") (pinfunction "DDR1_VDD_4_J14") (pintype "passive"))
      (node (ref "U8") (pin "J15") (pinfunction "DDR1_VDD_5_J15") (pintype "passive"))
      (node (ref "U8") (pin "J16") (pinfunction "DDR1_VDD_6_J16") (pintype "passive"))
      (node (ref "U8") (pin "J17") (pinfunction "DDR1_VDD_7_J17") (pintype "passive"))
      (node (ref "U8") (pin "J18") (pinfunction "DDR1_VDD_8_J18") (pintype "passive"))
      (node (ref "U8") (pin "K11") (pinfunction "DDR1_VDD_9_K11") (pintype "passive"))
      (node (ref "U8") (pin "K13") (pinfunction "DDR1_VDD_10_K13") (pintype "passive"))
      (node (ref "U8") (pin "K15") (pinfunction "DDR1_VDD_11_K15") (pintype "passive"))
      (node (ref "U8") (pin "K17") (pinfunction "DDR1_VDD_12_K17") (pintype "passive"))
      (node (ref "U8") (pin "L10") (pinfunction "DDR0_VDD_2_L10") (pintype "passive"))
      (node (ref "U8") (pin "L9") (pinfunction "DDR0_VDD_1_L9") (pintype "passive"))
      (node (ref "U8") (pin "M9") (pinfunction "DDR0_VDD_3_M9") (pintype "passive"))
      (node (ref "U8") (pin "N10") (pinfunction "DDR0_VDD_5_N10") (pintype "passive"))
      (node (ref "U8") (pin "N9") (pinfunction "DDR0_VDD_4_N9") (pintype "passive"))
      (node (ref "U8") (pin "P9") (pinfunction "DDR0_VDD_6_P9") (pintype "passive"))
      (node (ref "U8") (pin "R10") (pinfunction "DDR0_VDD_8_R10") (pintype "passive"))
      (node (ref "U8") (pin "R9") (pinfunction "DDR0_VDD_7_R9") (pintype "passive"))
      (node (ref "U8") (pin "T9") (pinfunction "DDR0_VDD_9_T9") (pintype "passive"))
      (node (ref "U8") (pin "U10") (pinfunction "DDR0_VDD_11_U10") (pintype "passive"))
      (node (ref "U8") (pin "U9") (pinfunction "DDR0_VDD_10_U9") (pintype "passive"))
      (node (ref "U8") (pin "V9") (pinfunction "DDR0_VDD_12_V9") (pintype "passive"))
    )
    (net (code "132") (name "unconnected-(U8D-DDR1_A6-PadB7)") (class "Default")
      (node (ref "U8") (pin "B7") (pinfunction "DDR1_A6_B7") (pintype "passive+no_connect"))
    )
    (net (code "133") (name "unconnected-(U8D-DDR1_A7-PadA7)") (class "Default")
      (node (ref "U8") (pin "A7") (pinfunction "DDR1_A7_A7") (pintype "passive+no_connect"))
    )
    (net (code "134") (name "unconnected-(U8D-DDR1_A8-PadB6)") (class "Default")
      (node (ref "U8") (pin "B6") (pinfunction "DDR1_A8_B6") (pintype "passive+no_connect"))
    )
    (net (code "135") (name "unconnected-(U8D-DDR1_A9-PadA6)") (class "Default")
      (node (ref "U8") (pin "A6") (pinfunction "DDR1_A9_A6") (pintype "passive+no_connect"))
    )
    (net (code "136") (name "unconnected-(U8D-DDR1_A10-PadA4)") (class "Default")
      (node (ref "U8") (pin "A4") (pinfunction "DDR1_A10_A4") (pintype "passive+no_connect"))
    )
    (net (code "137") (name "unconnected-(U8D-DDR1_A11-PadC5)") (class "Default")
      (node (ref "U8") (pin "C5") (pinfunction "DDR1_A11_C5") (pintype "passive+no_connect"))
    )
    (net (code "138") (name "unconnected-(U8D-DDR1_A12-PadA3)") (class "Default")
      (node (ref "U8") (pin "A3") (pinfunction "DDR1_A12_A3") (pintype "passive+no_connect"))
    )
    (net (code "139") (name "unconnected-(U8D-DDR1_A13-PadB4)") (class "Default")
      (node (ref "U8") (pin "B4") (pinfunction "DDR1_A13_B4") (pintype "passive+no_connect"))
    )
    (net (code "140") (name "unconnected-(U8D-DDR1_A14-PadC4)") (class "Default")
      (node (ref "U8") (pin "C4") (pinfunction "DDR1_A14_C4") (pintype "passive+no_connect"))
    )
    (net (code "141") (name "unconnected-(U8D-DDR1_A15-PadG8)") (class "Default")
      (node (ref "U8") (pin "G8") (pinfunction "DDR1_A15_G8") (pintype "passive+no_connect"))
    )
    (net (code "142") (name "unconnected-(U8D-DDR1_ATB0-PadF17)") (class "Default")
      (node (ref "U8") (pin "F17") (pinfunction "DDR1_ATB0_F17") (pintype "passive+no_connect"))
    )
    (net (code "143") (name "unconnected-(U8D-DDR1_ATB1-PadG17)") (class "Default")
      (node (ref "U8") (pin "G17") (pinfunction "DDR1_ATB1_G17") (pintype "passive+no_connect"))
    )
    (net (code "144") (name "unconnected-(U8D-DDR1_BA0-PadB2)") (class "Default")
      (node (ref "U8") (pin "B2") (pinfunction "DDR1_BA0_B2") (pintype "passive+no_connect"))
    )
    (net (code "145") (name "unconnected-(U8D-DDR1_BA1-PadD6)") (class "Default")
      (node (ref "U8") (pin "D6") (pinfunction "DDR1_BA1_D6") (pintype "passive+no_connect"))
    )
    (net (code "146") (name "unconnected-(U8D-DDR1_BA2-PadD12)") (class "Default")
      (node (ref "U8") (pin "D12") (pinfunction "DDR1_BA2_D12") (pintype "passive+no_connect"))
    )
    (net (code "147") (name "unconnected-(U8D-DDR1_CASn-PadF9)") (class "Default")
      (node (ref "U8") (pin "F9") (pinfunction "DDR1_CASn_F9") (pintype "passive+no_connect"))
    )
    (net (code "148") (name "unconnected-(U8D-DDR1_ODT0-PadD11)") (class "Default")
      (node (ref "U8") (pin "D11") (pinfunction "DDR1_ODT0_D11") (pintype "passive+no_connect"))
    )
    (net (code "149") (name "unconnected-(U8D-DDR1_ODT1-PadE11)") (class "Default")
      (node (ref "U8") (pin "E11") (pinfunction "DDR1_ODT1_E11") (pintype "passive+no_connect"))
    )
    (net (code "150") (name "unconnected-(U8D-DDR1_PLL_TESTOUT_N-PadG14)") (class "Default")
      (node (ref "U8") (pin "G14") (pinfunction "DDR1_PLL_TESTOUT_N_G14") (pintype "passive+no_connect"))
    )
    (net (code "151") (name "unconnected-(U8D-DDR1_PLL_TESTOUT_P-PadF14)") (class "Default")
      (node (ref "U8") (pin "F14") (pinfunction "DDR1_PLL_TESTOUT_P_F14") (pintype "passive+no_connect"))
    )
    (net (code "152") (name "unconnected-(U8D-DDR1_RASn-PadC6)") (class "Default")
      (node (ref "U8") (pin "C6") (pinfunction "DDR1_RASn_C6") (pintype "passive+no_connect"))
    )
    (net (code "153") (name "unconnected-(U8D-DDR1_WEn-PadF7)") (class "Default")
      (node (ref "U8") (pin "F7") (pinfunction "DDR1_WEn_F7") (pintype "passive+no_connect"))
    )
    (net (code "154") (name "unconnected-(U8E-DDR0_A6-PadJ1)") (class "Default")
      (node (ref "U8") (pin "J1") (pinfunction "DDR0_A6_J1") (pintype "passive+no_connect"))
    )
    (net (code "155") (name "unconnected-(U8E-DDR0_A7-PadJ2)") (class "Default")
      (node (ref "U8") (pin "J2") (pinfunction "DDR0_A7_J2") (pintype "passive+no_connect"))
    )
    (net (code "156") (name "unconnected-(U8E-DDR0_A8-PadK2)") (class "Default")
      (node (ref "U8") (pin "K2") (pinfunction "DDR0_A8_K2") (pintype "passive+no_connect"))
    )
    (net (code "157") (name "unconnected-(U8E-DDR0_A9-PadK1)") (class "Default")
      (node (ref "U8") (pin "K1") (pinfunction "DDR0_A9_K1") (pintype "passive+no_connect"))
    )
    (net (code "158") (name "unconnected-(U8E-DDR0_A10-PadD1)") (class "Default")
      (node (ref "U8") (pin "D1") (pinfunction "DDR0_A10_D1") (pintype "passive+no_connect"))
    )
    (net (code "159") (name "unconnected-(U8E-DDR0_A11-PadE3)") (class "Default")
      (node (ref "U8") (pin "E3") (pinfunction "DDR0_A11_E3") (pintype "passive+no_connect"))
    )
    (net (code "160") (name "unconnected-(U8E-DDR0_A12-PadC1)") (class "Default")
      (node (ref "U8") (pin "C1") (pinfunction "DDR0_A12_C1") (pintype "passive+no_connect"))
    )
    (net (code "161") (name "unconnected-(U8E-DDR0_A13-PadD2)") (class "Default")
      (node (ref "U8") (pin "D2") (pinfunction "DDR0_A13_D2") (pintype "passive+no_connect"))
    )
    (net (code "162") (name "unconnected-(U8E-DDR0_A14-PadD3)") (class "Default")
      (node (ref "U8") (pin "D3") (pinfunction "DDR0_A14_D3") (pintype "passive+no_connect"))
    )
    (net (code "163") (name "unconnected-(U8E-DDR0_A15-PadH7)") (class "Default")
      (node (ref "U8") (pin "H7") (pinfunction "DDR0_A15_H7") (pintype "passive+no_connect"))
    )
    (net (code "164") (name "unconnected-(U8E-DDR0_ATB0-PadU6)") (class "Default")
      (node (ref "U8") (pin "U6") (pinfunction "DDR0_ATB0_U6") (pintype "passive+no_connect"))
    )
    (net (code "165") (name "unconnected-(U8E-DDR0_ATB1-PadU7)") (class "Default")
      (node (ref "U8") (pin "U7") (pinfunction "DDR0_ATB1_U7") (pintype "passive+no_connect"))
    )
    (net (code "166") (name "unconnected-(U8E-DDR0_BA0-PadC3)") (class "Default")
      (node (ref "U8") (pin "C3") (pinfunction "DDR0_BA0_C3") (pintype "passive+no_connect"))
    )
    (net (code "167") (name "unconnected-(U8E-DDR0_BA1-PadF4)") (class "Default")
      (node (ref "U8") (pin "F4") (pinfunction "DDR0_BA1_F4") (pintype "passive+no_connect"))
    )
    (net (code "168") (name "unconnected-(U8E-DDR0_BA2-PadM4)") (class "Default")
      (node (ref "U8") (pin "M4") (pinfunction "DDR0_BA2_M4") (pintype "passive+no_connect"))
    )
    (net (code "169") (name "unconnected-(U8E-DDR0_CASn-PadH6)") (class "Default")
      (node (ref "U8") (pin "H6") (pinfunction "DDR0_CASn_H6") (pintype "passive+no_connect"))
    )
    (net (code "170") (name "unconnected-(U8E-DDR0_ODT0-PadL4)") (class "Default")
      (node (ref "U8") (pin "L4") (pinfunction "DDR0_ODT0_L4") (pintype "passive+no_connect"))
    )
    (net (code "171") (name "unconnected-(U8E-DDR0_ODT1-PadL5)") (class "Default")
      (node (ref "U8") (pin "L5") (pinfunction "DDR0_ODT1_L5") (pintype "passive+no_connect"))
    )
    (net (code "172") (name "unconnected-(U8E-DDR0_PLL_TESTOUT_N-PadV7)") (class "Default")
      (node (ref "U8") (pin "V7") (pinfunction "DDR0_PLL_TESTOUT_N_V7") (pintype "passive+no_connect"))
    )
    (net (code "173") (name "unconnected-(U8E-DDR0_PLL_TESTOUT_P-PadV6)") (class "Default")
      (node (ref "U8") (pin "V6") (pinfunction "DDR0_PLL_TESTOUT_P_V6") (pintype "passive+no_connect"))
    )
    (net (code "174") (name "unconnected-(U8E-DDR0_RASn-PadF3)") (class "Default")
      (node (ref "U8") (pin "F3") (pinfunction "DDR0_RASn_F3") (pintype "passive+no_connect"))
    )
    (net (code "175") (name "unconnected-(U8E-DDR0_WEn-PadG6)") (class "Default")
      (node (ref "U8") (pin "G6") (pinfunction "DDR0_WEn_G6") (pintype "passive+no_connect"))
    )
  )
)
